# power.net
KiCad netlist of a schematic drawn in Altium Designer
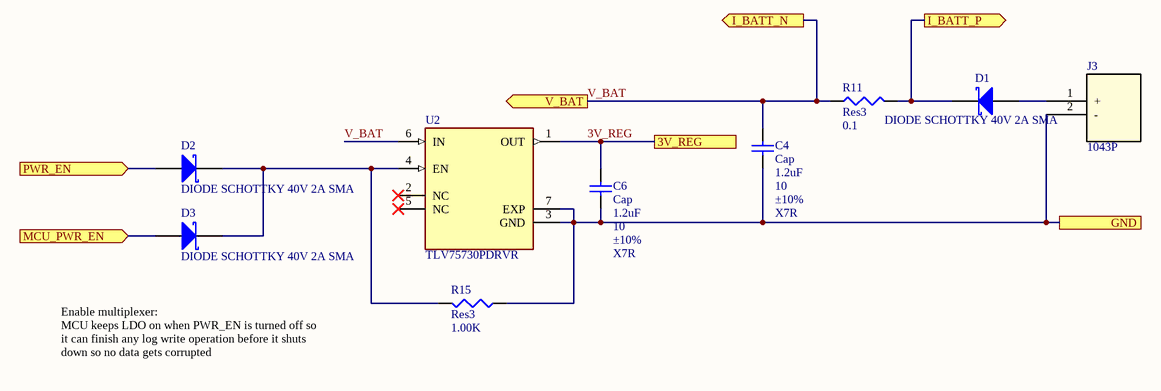
[diagram p0: power.SchDoc]

(export (version "E")
  (design (tool "Eeschema 10.0.6"))
  (components
    (comp (ref "C4")
      (value "Cap")
      (footprint "CAPC2012X09M")
      (description "CAP CER 1.2uF 10v X7R 0805")
      (fields
        (field (name "ALTIUM_VALUE") "1.2uF")
        (field (name "WV") "10")
        (field (name "TOLERANCE") "±10%")
        (field (name "TYPE") "X7R")
        (field (name "MPN") "C0805C125K8RACTU")
      )
      (libsource (lib "esd_library") (part "CAP-X7R-1.2uF-10V-±10%"))
    )
    (comp (ref "C6")
      (value "Cap")
      (footprint "CAPC2012X09M")
      (description "CAP CER 1.2uF 10v X7R 0805")
      (fields
        (field (name "ALTIUM_VALUE") "1.2uF")
        (field (name "WV") "10")
        (field (name "TOLERANCE") "±10%")
        (field (name "TYPE") "X7R")
        (field (name "MPN") "C0805C125K8RACTU")
      )
      (libsource (lib "esd_library") (part "CAP-X7R-1.2uF-10V-±10%"))
    )
    (comp (ref "D1")
      (value "DIODE SCHOTTKY 40V 2A SMA")
      (footprint "DIOM4326X23M")
      (description "Schottky Rectifier")
      (fields (field (name "MPN") "B240A-13-F"))
      (libsource (lib "esd_library") (part "DIODE SCHOTTKY 40V 2A SMA"))
    )
    (comp (ref "D2")
      (value "DIODE SCHOTTKY 40V 2A SMA")
      (footprint "DIOM4326X23M")
      (description "Schottky Rectifier")
      (fields (field (name "MPN") "B240A-13-F"))
      (libsource (lib "esd_library") (part "DIODE SCHOTTKY 40V 2A SMA"))
    )
    (comp (ref "D3")
      (value "DIODE SCHOTTKY 40V 2A SMA")
      (footprint "DIOM4326X23M")
      (description "Schottky Rectifier")
      (fields (field (name "MPN") "B240A-13-F"))
      (libsource (lib "esd_library") (part "DIODE SCHOTTKY 40V 2A SMA"))
    )
    (comp (ref "J3")
      (value "1043P")
      (footprint "CONN2_1043P_KEY")
      (description "No Description Available")
      (fields (field (name "COPYRIGHT") "Copyright (C) 2022 Ultra Librarian. All rights reserved."))
      (libsource (lib "1043P") (part "1043P"))
    )
    (comp (ref "R11")
      (value "Res3")
      (footprint "RESC2112X05M")
      (description "RES SMD 0.1 OHM 5% 1/8W 0805")
      (fields (field (name "MPN") "CRCW08050000Z0EA") (field (name "ALTIUM_VALUE") "0.1"))
      (libsource (lib "esd_library") (part "Resistor_0R_Jumper"))
    )
    (comp (ref "R15")
      (value "Res3")
      (footprint "RESC2112X05M")
      (description "RES SMD 1.00K OHM 1% 1/8W 0805")
      (fields (field (name "ALTIUM_VALUE") "1.00K") (field (name "MPN") "CRCW08051K00FKEA"))
      (libsource (lib "esd_library") (part "Resistor_1.00K"))
    )
    (comp (ref "U2")
      (value "TLV75730PDRVR")
      (footprint "VREG_TLV75730PDRVR")
      (description "1-A, low-IQ, high-accuracy, low-dropout voltage regulator with enable")
      (fields (field (name "MF") "Texas Instruments") (field (name "DIGI-KEY_PART_NUMBER") "296-50008-2-ND"))
      (libsource (lib "TLV75730PDRVR") (part "TLV75730PDRVR"))
    )
  )
  (nets
    (net (code "1") (name "/3V_REG") (class "Default")
      (node (ref "C6") (pin "2") (pinfunction "2_2") (pintype "passive"))
      (node (ref "U2") (pin "1") (pinfunction "OUT_1") (pintype "output"))
    )
    (net (code "2") (name "/GND") (class "Default")
      (node (ref "C4") (pin "1") (pinfunction "1_1") (pintype "passive"))
      (node (ref "C6") (pin "1") (pinfunction "1_1") (pintype "passive"))
      (node (ref "J3") (pin "2") (pinfunction "-_2") (pintype "passive"))
      (node (ref "R15") (pin "1") (pinfunction "1_1") (pintype "passive"))
      (node (ref "U2") (pin "3") (pinfunction "GND_3") (pintype "power_in"))
      (node (ref "U2") (pin "7") (pinfunction "EXP_7") (pintype "power_in"))
    )
    (net (code "3") (name "/I_BATT_P") (class "Default")
      (node (ref "D1") (pin "1") (pinfunction "K_1") (pintype "passive"))
      (node (ref "R11") (pin "2") (pinfunction "2_2") (pintype "passive"))
    )
    (net (code "4") (name "/MCU_PWR_EN") (class "Default")
      (node (ref "D3") (pin "2") (pinfunction "A_2") (pintype "passive"))
    )
    (net (code "5") (name "/PWR_EN") (class "Default")
      (node (ref "D2") (pin "2") (pinfunction "A_2") (pintype "passive"))
    )
    (net (code "6") (name "/V_BAT") (class "Default")
      (node (ref "C4") (pin "2") (pinfunction "2_2") (pintype "passive"))
      (node (ref "R11") (pin "1") (pinfunction "1_1") (pintype "passive"))
      (node (ref "U2") (pin "6") (pinfunction "IN_6") (pintype "input"))
    )
    (net (code "7") (name "Net-(D1-A)") (class "Default")
      (node (ref "D1") (pin "2") (pinfunction "A_2") (pintype "passive"))
      (node (ref "J3") (pin "1") (pinfunction "+_1") (pintype "passive"))
    )
    (net (code "8") (name "Net-(D2-K)") (class "Default")
      (node (ref "D2") (pin "1") (pinfunction "K_1") (pintype "passive"))
      (node (ref "D3") (pin "1") (pinfunction "K_1") (pintype "passive"))
      (node (ref "R15") (pin "2") (pinfunction "2_2") (pintype "passive"))
      (node (ref "U2") (pin "4") (pinfunction "EN_4") (pintype "input"))
    )
    (net (code "9") (name "unconnected-(U2-NC-Pad2)") (class "Default")
      (node (ref "U2") (pin "2") (pinfunction "NC_2") (pintype "passive+no_connect"))
    )
    (net (code "10") (name "unconnected-(U2-NC-Pad5)") (class "Default")
      (node (ref "U2") (pin "5") (pinfunction "NC_5") (pintype "passive+no_connect"))
    )
  )
)
